# snorlax.net
KiCad netlist of a schematic drawn in EAGLE
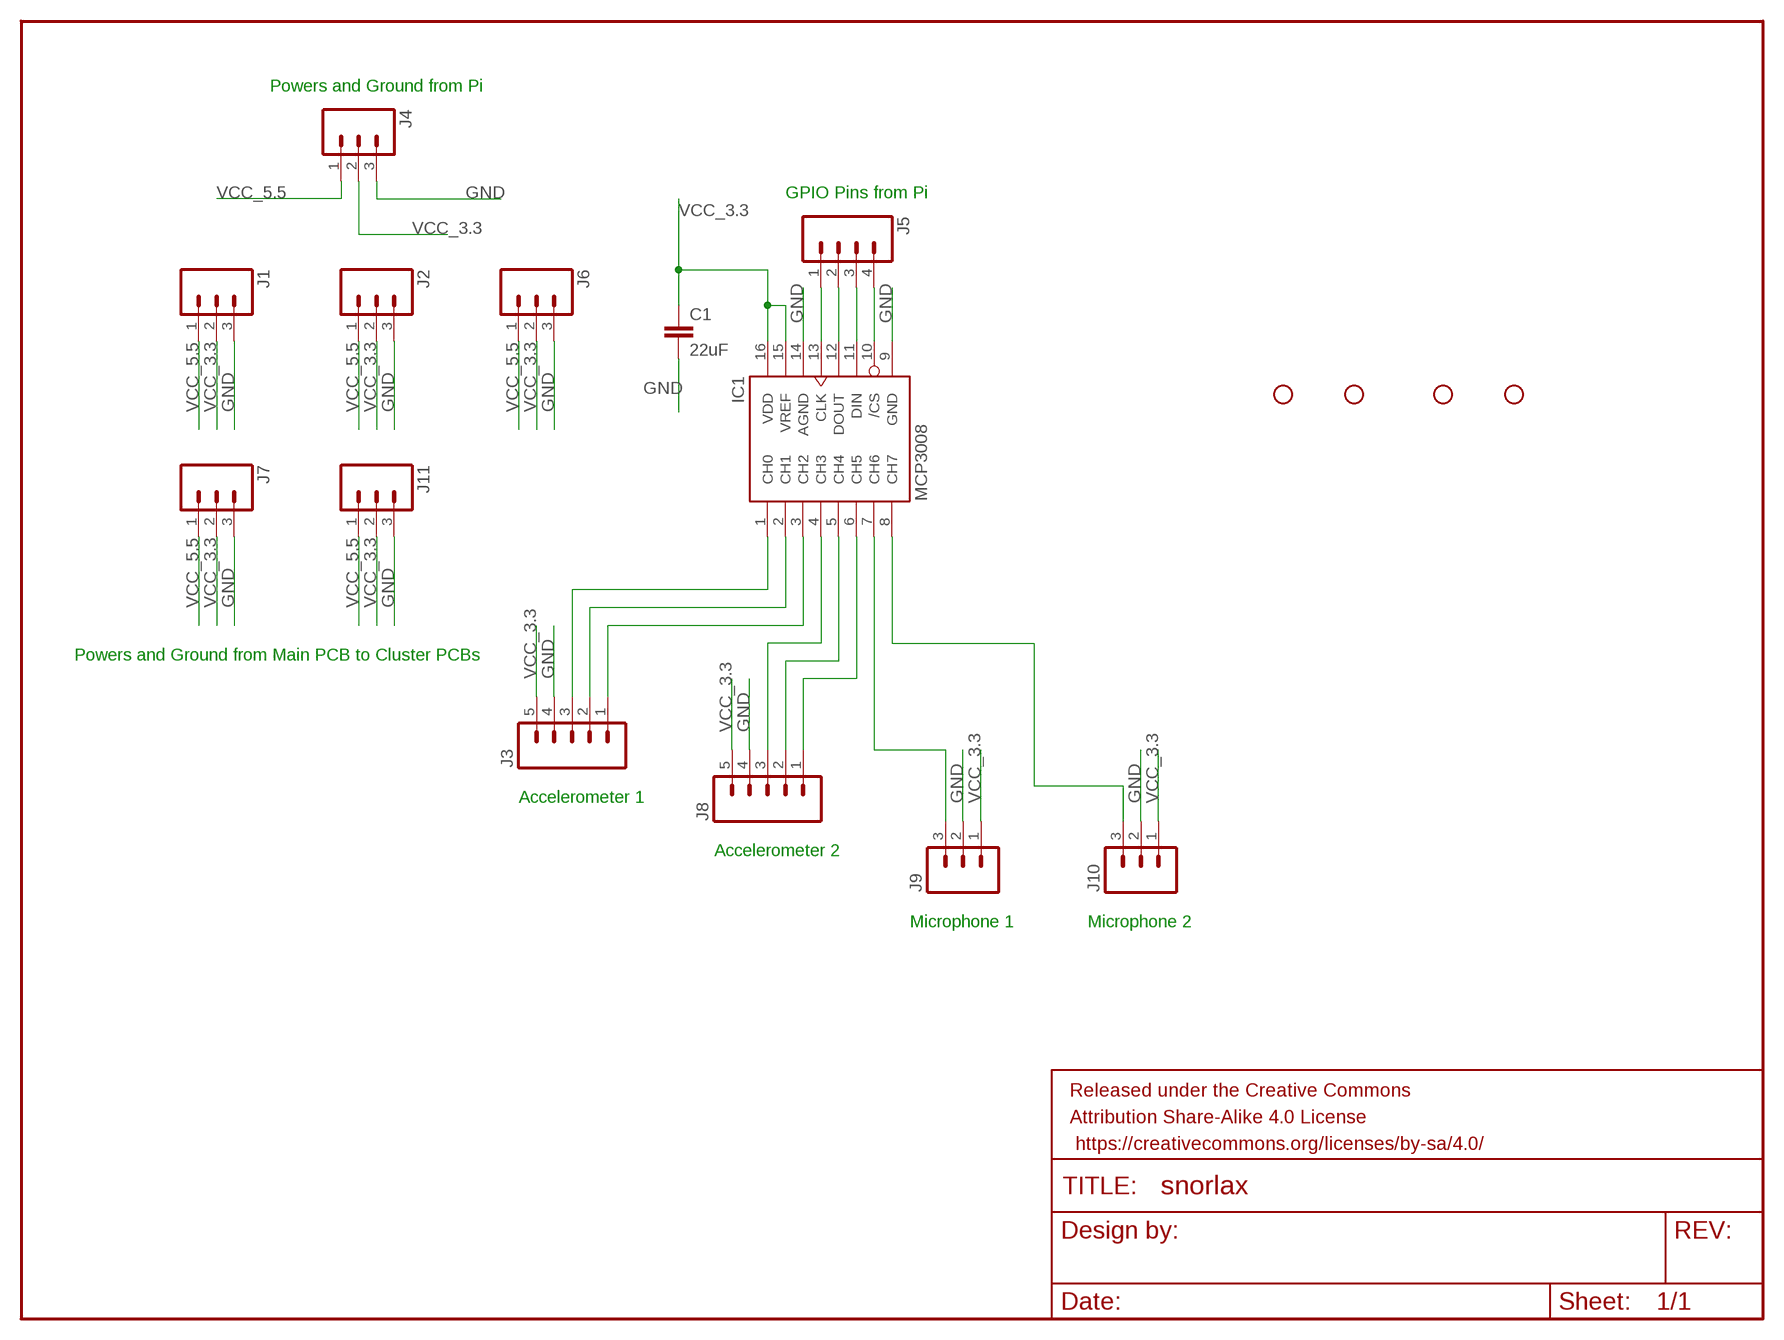
[diagram p0: schematic, sheet 1]

(export (version "E")
  (design (tool "Eeschema 10.0.6"))
  (components
    (comp (ref "C1")
      (value "22uF")
      (footprint "eagle-import:1206")
      (libsource (lib "eagle-import") (part "CAP1206"))
    )
    (comp (ref "FRAME1")
      (value "FRAME-LETTER")
      (footprint "eagle-import:CREATIVE_COMMONS")
      (libsource (lib "eagle-import") (part "FRAME-LETTER"))
    )
    (comp (ref "H1")
      (value "STAND-OFF")
      (footprint "eagle-import:STAND-OFF")
      (libsource (lib "eagle-import") (part "STAND-OFF"))
    )
    (comp (ref "H2")
      (value "STAND-OFF")
      (footprint "eagle-import:STAND-OFF")
      (libsource (lib "eagle-import") (part "STAND-OFF"))
    )
    (comp (ref "H3")
      (value "STAND-OFF")
      (footprint "eagle-import:STAND-OFF")
      (libsource (lib "eagle-import") (part "STAND-OFF"))
    )
    (comp (ref "H4")
      (value "STAND-OFF")
      (footprint "eagle-import:STAND-OFF")
      (libsource (lib "eagle-import") (part "STAND-OFF"))
    )
    (comp (ref "IC1")
      (value "MCP3008")
      (footprint "eagle-import:DIL16")
      (libsource (lib "eagle-import") (part "MCP3008"))
    )
    (comp (ref "J1")
      (value "M03LOCK")
      (footprint "eagle-import:1X03_LOCK")
      (libsource (lib "eagle-import") (part "M03LOCK"))
    )
    (comp (ref "J2")
      (value "M03LOCK")
      (footprint "eagle-import:1X03_LOCK")
      (libsource (lib "eagle-import") (part "M03LOCK"))
    )
    (comp (ref "J3")
      (value "M05LOCK")
      (footprint "eagle-import:1X05_LOCK")
      (libsource (lib "eagle-import") (part "M05LOCK"))
    )
    (comp (ref "J4")
      (value "M03LOCK")
      (footprint "eagle-import:1X03_LOCK")
      (libsource (lib "eagle-import") (part "M03LOCK"))
    )
    (comp (ref "J5")
      (value "M04LOCK")
      (footprint "eagle-import:1X04_LOCK")
      (libsource (lib "eagle-import") (part "M04LOCK"))
    )
    (comp (ref "J6")
      (value "M03LOCK")
      (footprint "eagle-import:1X03_LOCK")
      (libsource (lib "eagle-import") (part "M03LOCK"))
    )
    (comp (ref "J7")
      (value "M03LOCK")
      (footprint "eagle-import:1X03_LOCK")
      (libsource (lib "eagle-import") (part "M03LOCK"))
    )
    (comp (ref "J8")
      (value "M05LOCK")
      (footprint "eagle-import:1X05_LOCK")
      (libsource (lib "eagle-import") (part "M05LOCK"))
    )
    (comp (ref "J9")
      (value "M03LOCK")
      (footprint "eagle-import:1X03_LOCK")
      (libsource (lib "eagle-import") (part "M03LOCK"))
    )
    (comp (ref "J10")
      (value "M03LOCK")
      (footprint "eagle-import:1X03_LOCK")
      (libsource (lib "eagle-import") (part "M03LOCK"))
    )
    (comp (ref "J11")
      (value "M03LOCK")
      (footprint "eagle-import:1X03_LOCK")
      (libsource (lib "eagle-import") (part "M03LOCK"))
    )
  )
  (nets
    (net (code "1") (name "/GND") (class "Default")
      (node (ref "C1") (pin "2") (pinfunction "2_2") (pintype "passive"))
      (node (ref "IC1") (pin "14") (pinfunction "AGND_14") (pintype "power_in"))
      (node (ref "IC1") (pin "9") (pinfunction "GND_9") (pintype "power_in"))
      (node (ref "J1") (pin "3") (pinfunction "3_3") (pintype "passive"))
      (node (ref "J10") (pin "2") (pinfunction "2_2") (pintype "passive"))
      (node (ref "J11") (pin "3") (pinfunction "3_3") (pintype "passive"))
      (node (ref "J2") (pin "3") (pinfunction "3_3") (pintype "passive"))
      (node (ref "J3") (pin "4") (pinfunction "4_4") (pintype "passive"))
      (node (ref "J4") (pin "3") (pinfunction "3_3") (pintype "passive"))
      (node (ref "J6") (pin "3") (pinfunction "3_3") (pintype "passive"))
      (node (ref "J7") (pin "3") (pinfunction "3_3") (pintype "passive"))
      (node (ref "J8") (pin "4") (pinfunction "4_4") (pintype "passive"))
      (node (ref "J9") (pin "2") (pinfunction "2_2") (pintype "passive"))
    )
    (net (code "2") (name "/VCC_3.3") (class "Default")
      (node (ref "C1") (pin "1") (pinfunction "1_1") (pintype "passive"))
      (node (ref "IC1") (pin "15") (pinfunction "VREF_15") (pintype "input"))
      (node (ref "IC1") (pin "16") (pinfunction "VDD_16") (pintype "power_in"))
      (node (ref "J1") (pin "2") (pinfunction "2_2") (pintype "passive"))
      (node (ref "J10") (pin "1") (pinfunction "1_1") (pintype "passive"))
      (node (ref "J11") (pin "2") (pinfunction "2_2") (pintype "passive"))
      (node (ref "J2") (pin "2") (pinfunction "2_2") (pintype "passive"))
      (node (ref "J3") (pin "5") (pinfunction "5_5") (pintype "passive"))
      (node (ref "J4") (pin "2") (pinfunction "2_2") (pintype "passive"))
      (node (ref "J6") (pin "2") (pinfunction "2_2") (pintype "passive"))
      (node (ref "J7") (pin "2") (pinfunction "2_2") (pintype "passive"))
      (node (ref "J8") (pin "5") (pinfunction "5_5") (pintype "passive"))
      (node (ref "J9") (pin "1") (pinfunction "1_1") (pintype "passive"))
    )
    (net (code "3") (name "/VCC_5.5") (class "Default")
      (node (ref "J1") (pin "1") (pinfunction "1_1") (pintype "passive"))
      (node (ref "J11") (pin "1") (pinfunction "1_1") (pintype "passive"))
      (node (ref "J2") (pin "1") (pinfunction "1_1") (pintype "passive"))
      (node (ref "J4") (pin "1") (pinfunction "1_1") (pintype "passive"))
      (node (ref "J6") (pin "1") (pinfunction "1_1") (pintype "passive"))
      (node (ref "J7") (pin "1") (pinfunction "1_1") (pintype "passive"))
    )
    (net (code "4") (name "Net-(IC1-CH0)") (class "Default")
      (node (ref "IC1") (pin "1") (pinfunction "CH0_1") (pintype "input"))
      (node (ref "J3") (pin "3") (pinfunction "3_3") (pintype "passive"))
    )
    (net (code "5") (name "Net-(IC1-CH1)") (class "Default")
      (node (ref "IC1") (pin "2") (pinfunction "CH1_2") (pintype "input"))
      (node (ref "J3") (pin "2") (pinfunction "2_2") (pintype "passive"))
    )
    (net (code "6") (name "Net-(IC1-CH2)") (class "Default")
      (node (ref "IC1") (pin "3") (pinfunction "CH2_3") (pintype "input"))
      (node (ref "J3") (pin "1") (pinfunction "1_1") (pintype "passive"))
    )
    (net (code "7") (name "Net-(IC1-CH3)") (class "Default")
      (node (ref "IC1") (pin "4") (pinfunction "CH3_4") (pintype "input"))
      (node (ref "J8") (pin "3") (pinfunction "3_3") (pintype "passive"))
    )
    (net (code "8") (name "Net-(IC1-CH4)") (class "Default")
      (node (ref "IC1") (pin "5") (pinfunction "CH4_5") (pintype "input"))
      (node (ref "J8") (pin "2") (pinfunction "2_2") (pintype "passive"))
    )
    (net (code "9") (name "Net-(IC1-CH5)") (class "Default")
      (node (ref "IC1") (pin "6") (pinfunction "CH5_6") (pintype "input"))
      (node (ref "J8") (pin "1") (pinfunction "1_1") (pintype "passive"))
    )
    (net (code "10") (name "Net-(IC1-CH6)") (class "Default")
      (node (ref "IC1") (pin "7") (pinfunction "CH6_7") (pintype "input"))
      (node (ref "J9") (pin "3") (pinfunction "3_3") (pintype "passive"))
    )
    (net (code "11") (name "Net-(IC1-CH7)") (class "Default")
      (node (ref "IC1") (pin "8") (pinfunction "CH7_8") (pintype "input"))
      (node (ref "J10") (pin "3") (pinfunction "3_3") (pintype "passive"))
    )
    (net (code "12") (name "Net-(IC1-CLK)") (class "Default")
      (node (ref "IC1") (pin "13") (pinfunction "CLK_13") (pintype "input"))
      (node (ref "J5") (pin "1") (pinfunction "1_1") (pintype "passive"))
    )
    (net (code "13") (name "Net-(IC1-DIN)") (class "Default")
      (node (ref "IC1") (pin "11") (pinfunction "DIN_11") (pintype "input"))
      (node (ref "J5") (pin "3") (pinfunction "3_3") (pintype "passive"))
    )
    (net (code "14") (name "Net-(IC1-DOUT)") (class "Default")
      (node (ref "IC1") (pin "12") (pinfunction "DOUT_12") (pintype "output"))
      (node (ref "J5") (pin "2") (pinfunction "2_2") (pintype "passive"))
    )
    (net (code "15") (name "Net-(IC1-{slash}CS)") (class "Default")
      (node (ref "IC1") (pin "10") (pinfunction "/CS_10") (pintype "input"))
      (node (ref "J5") (pin "4") (pinfunction "4_4") (pintype "passive"))
    )
  )
)
